# Connector.net
KiCad netlist of a schematic drawn in Altium Designer
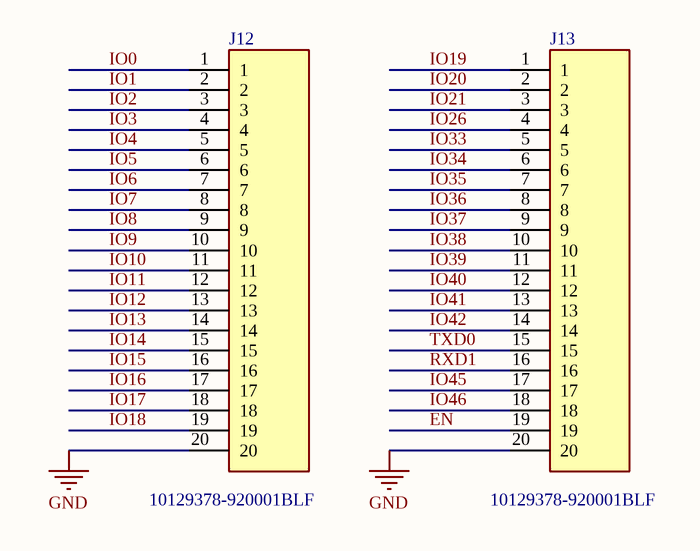
[diagram p0: Connector.SchDoc]

(export (version "E")
  (design (tool "Eeschema 10.0.6"))
  (components
    (comp (ref "J12")
      (value "10129378-920001BLF")
      (footprint "SamacSys:HDRV20W67P0X254_1X20_5080X241X858P")
      (description "Connector")
      (libsource (lib "Main") (part "10129378-920001BLF"))
    )
    (comp (ref "J13")
      (value "10129378-920001BLF")
      (footprint "SamacSys:HDRV20W67P0X254_1X20_5080X241X858P")
      (description "Connector")
      (libsource (lib "Main") (part "10129378-920001BLF"))
    )
  )
  (nets
    (net (code "1") (name "/EN") (class "Default")
      (node (ref "J13") (pin "19") (pinfunction "19_19") (pintype "passive"))
    )
    (net (code "2") (name "/IO0") (class "Default")
      (node (ref "J12") (pin "1") (pinfunction "1_1") (pintype "passive"))
    )
    (net (code "3") (name "/IO1") (class "Default")
      (node (ref "J12") (pin "2") (pinfunction "2_2") (pintype "passive"))
    )
    (net (code "4") (name "/IO2") (class "Default")
      (node (ref "J12") (pin "3") (pinfunction "3_3") (pintype "passive"))
    )
    (net (code "5") (name "/IO3") (class "Default")
      (node (ref "J12") (pin "4") (pinfunction "4_4") (pintype "passive"))
    )
    (net (code "6") (name "/IO4") (class "Default")
      (node (ref "J12") (pin "5") (pinfunction "5_5") (pintype "passive"))
    )
    (net (code "7") (name "/IO5") (class "Default")
      (node (ref "J12") (pin "6") (pinfunction "6_6") (pintype "passive"))
    )
    (net (code "8") (name "/IO6") (class "Default")
      (node (ref "J12") (pin "7") (pinfunction "7_7") (pintype "passive"))
    )
    (net (code "9") (name "/IO7") (class "Default")
      (node (ref "J12") (pin "8") (pinfunction "8_8") (pintype "passive"))
    )
    (net (code "10") (name "/IO8") (class "Default")
      (node (ref "J12") (pin "9") (pinfunction "9_9") (pintype "passive"))
    )
    (net (code "11") (name "/IO9") (class "Default")
      (node (ref "J12") (pin "10") (pinfunction "10_10") (pintype "passive"))
    )
    (net (code "12") (name "/IO10") (class "Default")
      (node (ref "J12") (pin "11") (pinfunction "11_11") (pintype "passive"))
    )
    (net (code "13") (name "/IO11") (class "Default")
      (node (ref "J12") (pin "12") (pinfunction "12_12") (pintype "passive"))
    )
    (net (code "14") (name "/IO12") (class "Default")
      (node (ref "J12") (pin "13") (pinfunction "13_13") (pintype "passive"))
    )
    (net (code "15") (name "/IO13") (class "Default")
      (node (ref "J12") (pin "14") (pinfunction "14_14") (pintype "passive"))
    )
    (net (code "16") (name "/IO14") (class "Default")
      (node (ref "J12") (pin "15") (pinfunction "15_15") (pintype "passive"))
    )
    (net (code "17") (name "/IO15") (class "Default")
      (node (ref "J12") (pin "16") (pinfunction "16_16") (pintype "passive"))
    )
    (net (code "18") (name "/IO16") (class "Default")
      (node (ref "J12") (pin "17") (pinfunction "17_17") (pintype "passive"))
    )
    (net (code "19") (name "/IO17") (class "Default")
      (node (ref "J12") (pin "18") (pinfunction "18_18") (pintype "passive"))
    )
    (net (code "20") (name "/IO18") (class "Default")
      (node (ref "J12") (pin "19") (pinfunction "19_19") (pintype "passive"))
    )
    (net (code "21") (name "/IO19") (class "Default")
      (node (ref "J13") (pin "1") (pinfunction "1_1") (pintype "passive"))
    )
    (net (code "22") (name "/IO20") (class "Default")
      (node (ref "J13") (pin "2") (pinfunction "2_2") (pintype "passive"))
    )
    (net (code "23") (name "/IO21") (class "Default")
      (node (ref "J13") (pin "3") (pinfunction "3_3") (pintype "passive"))
    )
    (net (code "24") (name "/IO26") (class "Default")
      (node (ref "J13") (pin "4") (pinfunction "4_4") (pintype "passive"))
    )
    (net (code "25") (name "/IO33") (class "Default")
      (node (ref "J13") (pin "5") (pinfunction "5_5") (pintype "passive"))
    )
    (net (code "26") (name "/IO34") (class "Default")
      (node (ref "J13") (pin "6") (pinfunction "6_6") (pintype "passive"))
    )
    (net (code "27") (name "/IO35") (class "Default")
      (node (ref "J13") (pin "7") (pinfunction "7_7") (pintype "passive"))
    )
    (net (code "28") (name "/IO36") (class "Default")
      (node (ref "J13") (pin "8") (pinfunction "8_8") (pintype "passive"))
    )
    (net (code "29") (name "/IO37") (class "Default")
      (node (ref "J13") (pin "9") (pinfunction "9_9") (pintype "passive"))
    )
    (net (code "30") (name "/IO38") (class "Default")
      (node (ref "J13") (pin "10") (pinfunction "10_10") (pintype "passive"))
    )
    (net (code "31") (name "/IO39") (class "Default")
      (node (ref "J13") (pin "11") (pinfunction "11_11") (pintype "passive"))
    )
    (net (code "32") (name "/IO40") (class "Default")
      (node (ref "J13") (pin "12") (pinfunction "12_12") (pintype "passive"))
    )
    (net (code "33") (name "/IO41") (class "Default")
      (node (ref "J13") (pin "13") (pinfunction "13_13") (pintype "passive"))
    )
    (net (code "34") (name "/IO42") (class "Default")
      (node (ref "J13") (pin "14") (pinfunction "14_14") (pintype "passive"))
    )
    (net (code "35") (name "/IO45") (class "Default")
      (node (ref "J13") (pin "17") (pinfunction "17_17") (pintype "passive"))
    )
    (net (code "36") (name "/IO46") (class "Default")
      (node (ref "J13") (pin "18") (pinfunction "18_18") (pintype "passive"))
    )
    (net (code "37") (name "/RXD1") (class "Default")
      (node (ref "J13") (pin "16") (pinfunction "16_16") (pintype "passive"))
    )
    (net (code "38") (name "/TXD0") (class "Default")
      (node (ref "J13") (pin "15") (pinfunction "15_15") (pintype "passive"))
    )
    (net (code "39") (name "GND") (class "Default")
      (node (ref "J12") (pin "20") (pinfunction "20_20") (pintype "passive"))
      (node (ref "J13") (pin "20") (pinfunction "20_20") (pintype "passive"))
    )
  )
)
